# local_osc.net
KiCad netlist of a schematic drawn in EAGLE
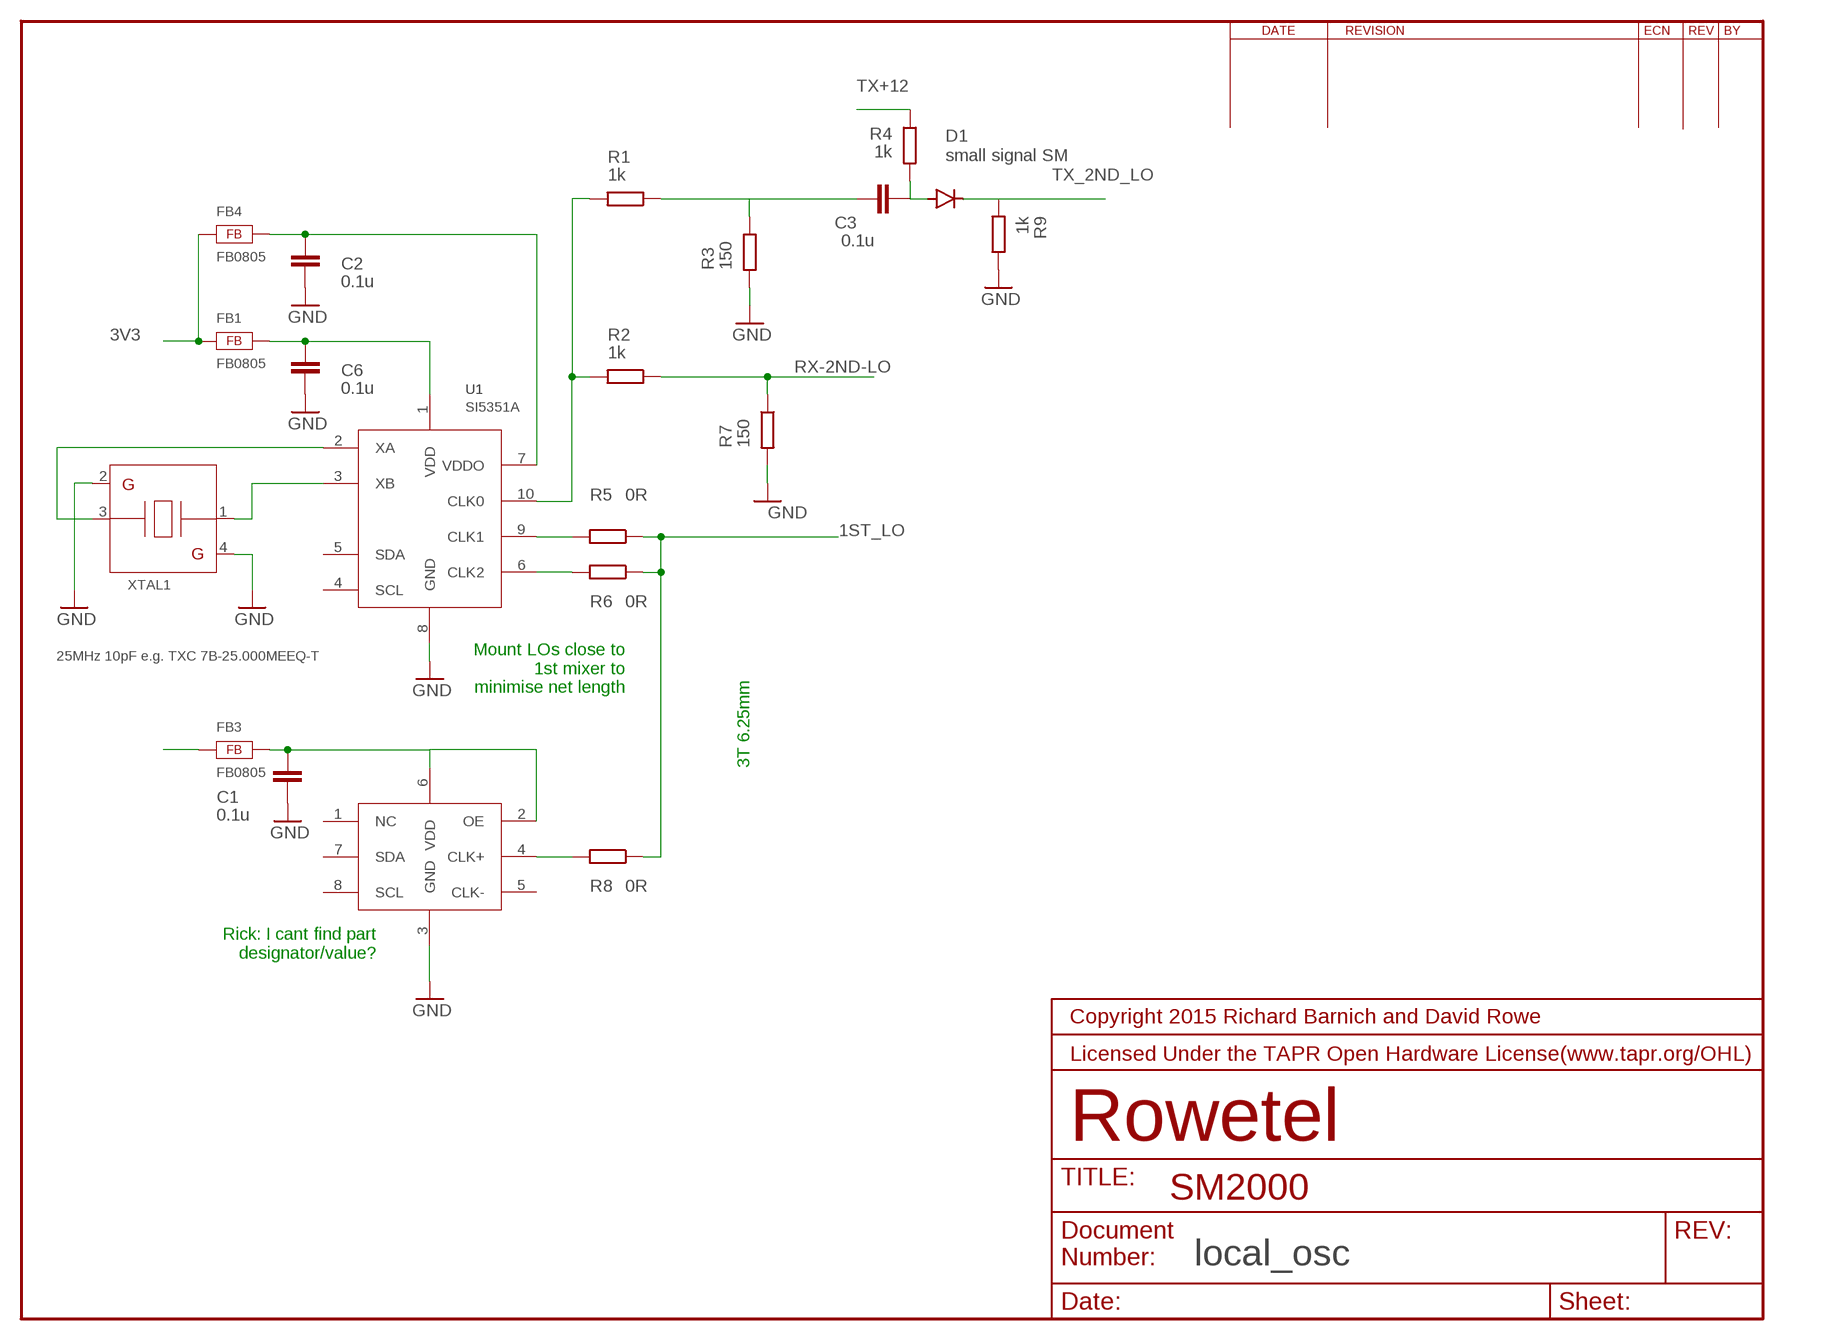
[diagram p0: schematic, sheet 1]

(export (version "E")
  (design (tool "Eeschema 10.0.6"))
  (components
    (comp (ref "C1")
      (value "0.1u")
      (footprint "eagle-import:C025-024X044")
      (libsource (lib "eagle-import") (part "C-EU025-024X044"))
    )
    (comp (ref "C2")
      (value "0.1u")
      (footprint "eagle-import:C025-024X044")
      (libsource (lib "eagle-import") (part "C-EU025-024X044"))
    )
    (comp (ref "C3")
      (value "0.1u")
      (footprint "eagle-import:C025-024X044")
      (libsource (lib "eagle-import") (part "C-EU025-024X044"))
    )
    (comp (ref "C6")
      (value "0.1u")
      (footprint "eagle-import:C025-024X044")
      (libsource (lib "eagle-import") (part "C-EU025-024X044"))
    )
    (comp (ref "D1")
      (value "small signal SM")
      (footprint "eagle-import:DO-214AC")
      (libsource (lib "eagle-import") (part "DIODE-DO-214AC"))
    )
    (comp (ref "FB1")
      (value "FB0805")
      (footprint "eagle-import:FE0805")
      (libsource (lib "eagle-import") (part "FB0805"))
    )
    (comp (ref "FB3")
      (value "FB0805")
      (footprint "eagle-import:FE0805")
      (libsource (lib "eagle-import") (part "FB0805"))
    )
    (comp (ref "FB4")
      (value "FB0805")
      (footprint "eagle-import:FE0805")
      (libsource (lib "eagle-import") (part "FB0805"))
    )
    (comp (ref "R1")
      (value "1k")
      (footprint "eagle-import:RESC2012X70N")
      (libsource (lib "eagle-import") (part "RESISTOR_0805"))
    )
    (comp (ref "R2")
      (value "1k")
      (footprint "eagle-import:RESC2012X70N")
      (libsource (lib "eagle-import") (part "RESISTOR_0805"))
    )
    (comp (ref "R3")
      (value "150")
      (footprint "eagle-import:RESC2012X70N")
      (libsource (lib "eagle-import") (part "RESISTOR_0805"))
    )
    (comp (ref "R4")
      (value "1k")
      (footprint "eagle-import:RESC2012X70N")
      (libsource (lib "eagle-import") (part "RESISTOR_0805"))
    )
    (comp (ref "R5")
      (value "0R")
      (footprint "eagle-import:RESC2012X70N")
      (libsource (lib "eagle-import") (part "RESISTOR_0805"))
    )
    (comp (ref "R6")
      (value "0R")
      (footprint "eagle-import:RESC2012X70N")
      (libsource (lib "eagle-import") (part "RESISTOR_0805"))
    )
    (comp (ref "R7")
      (value "150")
      (footprint "eagle-import:RESC2012X70N")
      (libsource (lib "eagle-import") (part "RESISTOR_0805"))
    )
    (comp (ref "R8")
      (value "0R")
      (footprint "eagle-import:RESC2012X70N")
      (libsource (lib "eagle-import") (part "RESISTOR_0805"))
    )
    (comp (ref "R9")
      (value "1k")
      (footprint "eagle-import:RESC2012X70N")
      (libsource (lib "eagle-import") (part "RESISTOR_0805"))
    )
    (comp (ref "U1")
      (value "SI5351A")
      (footprint "eagle-import:MSOP10")
      (libsource (lib "eagle-import") (part "SI5351A"))
    )
    (comp (ref "U2")
      (value "SI570CAC000141DG")
      (footprint "eagle-import:SI570")
      (libsource (lib "eagle-import") (part "SI570"))
    )
    (comp (ref "XTAL1")
      (value "25MHz 10pF e.g. TXC 7B-25.000MEEQ-T")
      (footprint "eagle-import:XTAL-FY0800035")
      (libsource (lib "eagle-import") (part "XTAL-FY0800035"))
    )
  )
  (nets
    (net (code "1") (name "/1ST_LO") (class "Default")
      (node (ref "R5") (pin "1") (pinfunction "1_1") (pintype "passive"))
      (node (ref "R6") (pin "1") (pinfunction "1_1") (pintype "passive"))
      (node (ref "R8") (pin "1") (pinfunction "1_1") (pintype "passive"))
    )
    (net (code "2") (name "/3V3") (class "Default")
      (node (ref "FB1") (pin "1") (pinfunction "1_1") (pintype "passive"))
      (node (ref "FB4") (pin "1") (pinfunction "1_1") (pintype "passive"))
    )
    (net (code "3") (name "/RX-2ND-LO") (class "Default")
      (node (ref "R2") (pin "1") (pinfunction "1_1") (pintype "passive"))
      (node (ref "R7") (pin "1") (pinfunction "1_1") (pintype "passive"))
    )
    (net (code "4") (name "/TX+12") (class "Default")
      (node (ref "R4") (pin "1") (pinfunction "1_1") (pintype "passive"))
    )
    (net (code "5") (name "/TX_2ND_LO") (class "Default")
      (node (ref "D1") (pin "C") (pinfunction "C_C") (pintype "passive"))
    )
    (net (code "6") (name "GND") (class "Default")
      (node (ref "C1") (pin "2") (pinfunction "2_2") (pintype "passive"))
      (node (ref "C2") (pin "2") (pinfunction "2_2") (pintype "passive"))
      (node (ref "C6") (pin "2") (pinfunction "2_2") (pintype "passive"))
      (node (ref "R3") (pin "2") (pinfunction "2_2") (pintype "passive"))
      (node (ref "R7") (pin "2") (pinfunction "2_2") (pintype "passive"))
      (node (ref "R9") (pin "1") (pinfunction "1_1") (pintype "passive"))
      (node (ref "U1") (pin "8") (pinfunction "GND_8") (pintype "power_in"))
      (node (ref "U2") (pin "3") (pinfunction "GND_3") (pintype "power_in"))
      (node (ref "XTAL1") (pin "2") (pinfunction "2_2") (pintype "bidirectional"))
      (node (ref "XTAL1") (pin "4") (pinfunction "4_4") (pintype "bidirectional"))
    )
    (net (code "7") (name "Net-(C3-Pad1)") (class "Default")
      (node (ref "C3") (pin "1") (pinfunction "1_1") (pintype "passive"))
      (node (ref "R1") (pin "1") (pinfunction "1_1") (pintype "passive"))
      (node (ref "R3") (pin "1") (pinfunction "1_1") (pintype "passive"))
    )
    (net (code "8") (name "Net-(C3-Pad2)") (class "Default")
      (node (ref "C3") (pin "2") (pinfunction "2_2") (pintype "passive"))
      (node (ref "D1") (pin "A") (pinfunction "A_A") (pintype "passive"))
      (node (ref "R4") (pin "2") (pinfunction "2_2") (pintype "passive"))
    )
    (net (code "9") (name "Net-(U1-CLK0)") (class "Default")
      (node (ref "R1") (pin "2") (pinfunction "2_2") (pintype "passive"))
      (node (ref "R2") (pin "2") (pinfunction "2_2") (pintype "passive"))
      (node (ref "U1") (pin "10") (pinfunction "CLK0_10") (pintype "output"))
    )
    (net (code "10") (name "Net-(U1-CLK1)") (class "Default")
      (node (ref "R5") (pin "2") (pinfunction "2_2") (pintype "passive"))
      (node (ref "U1") (pin "9") (pinfunction "CLK1_9") (pintype "output"))
    )
    (net (code "11") (name "Net-(U1-CLK2)") (class "Default")
      (node (ref "R6") (pin "2") (pinfunction "2_2") (pintype "passive"))
      (node (ref "U1") (pin "6") (pinfunction "CLK2_6") (pintype "output"))
    )
    (net (code "12") (name "Net-(U1-VDD)") (class "Default")
      (node (ref "C6") (pin "1") (pinfunction "1_1") (pintype "passive"))
      (node (ref "FB1") (pin "2") (pinfunction "2_2") (pintype "passive"))
      (node (ref "U1") (pin "1") (pinfunction "VDD_1") (pintype "power_in"))
    )
    (net (code "13") (name "Net-(U1-VDDO)") (class "Default")
      (node (ref "C2") (pin "1") (pinfunction "1_1") (pintype "passive"))
      (node (ref "FB4") (pin "2") (pinfunction "2_2") (pintype "passive"))
      (node (ref "U1") (pin "7") (pinfunction "VDDO_7") (pintype "power_in"))
    )
    (net (code "14") (name "Net-(U1-XA)") (class "Default")
      (node (ref "U1") (pin "2") (pinfunction "XA_2") (pintype "bidirectional"))
      (node (ref "XTAL1") (pin "3") (pinfunction "3_3") (pintype "bidirectional"))
    )
    (net (code "15") (name "Net-(U1-XB)") (class "Default")
      (node (ref "U1") (pin "3") (pinfunction "XB_3") (pintype "bidirectional"))
      (node (ref "XTAL1") (pin "1") (pinfunction "1_1") (pintype "bidirectional"))
    )
    (net (code "16") (name "Net-(U2-CLK+)") (class "Default")
      (node (ref "R8") (pin "2") (pinfunction "2_2") (pintype "passive"))
      (node (ref "U2") (pin "4") (pinfunction "CLK+_4") (pintype "output"))
    )
    (net (code "17") (name "Net-(U2-OE)") (class "Default")
      (node (ref "C1") (pin "1") (pinfunction "1_1") (pintype "passive"))
      (node (ref "FB3") (pin "2") (pinfunction "2_2") (pintype "passive"))
      (node (ref "U2") (pin "2") (pinfunction "OE_2") (pintype "input"))
      (node (ref "U2") (pin "6") (pinfunction "VDD_6") (pintype "power_in"))
    )
    (net (code "18") (name "unconnected-(FB3-Pad1)") (class "Default")
      (node (ref "FB3") (pin "1") (pinfunction "1_1") (pintype "passive"))
    )
    (net (code "19") (name "unconnected-(R9-Pad2)") (class "Default")
      (node (ref "R9") (pin "2") (pinfunction "2_2") (pintype "passive"))
    )
    (net (code "20") (name "unconnected-(U1-SCL-Pad4)") (class "Default")
      (node (ref "U1") (pin "4") (pinfunction "SCL_4") (pintype "bidirectional"))
    )
    (net (code "21") (name "unconnected-(U1-SDA-Pad5)") (class "Default")
      (node (ref "U1") (pin "5") (pinfunction "SDA_5") (pintype "bidirectional"))
    )
    (net (code "22") (name "unconnected-(U2-CLK--Pad5)") (class "Default")
      (node (ref "U2") (pin "5") (pinfunction "CLK-_5") (pintype "output"))
    )
    (net (code "23") (name "unconnected-(U2-NC-Pad1)") (class "Default")
      (node (ref "U2") (pin "1") (pinfunction "NC_1") (pintype "no_connect"))
    )
    (net (code "24") (name "unconnected-(U2-SCL-Pad8)") (class "Default")
      (node (ref "U2") (pin "8") (pinfunction "SCL_8") (pintype "bidirectional"))
    )
    (net (code "25") (name "unconnected-(U2-SDA-Pad7)") (class "Default")
      (node (ref "U2") (pin "7") (pinfunction "SDA_7") (pintype "bidirectional"))
    )
  )
)
